# Main.net
KiCad netlist of a schematic drawn in Altium Designer
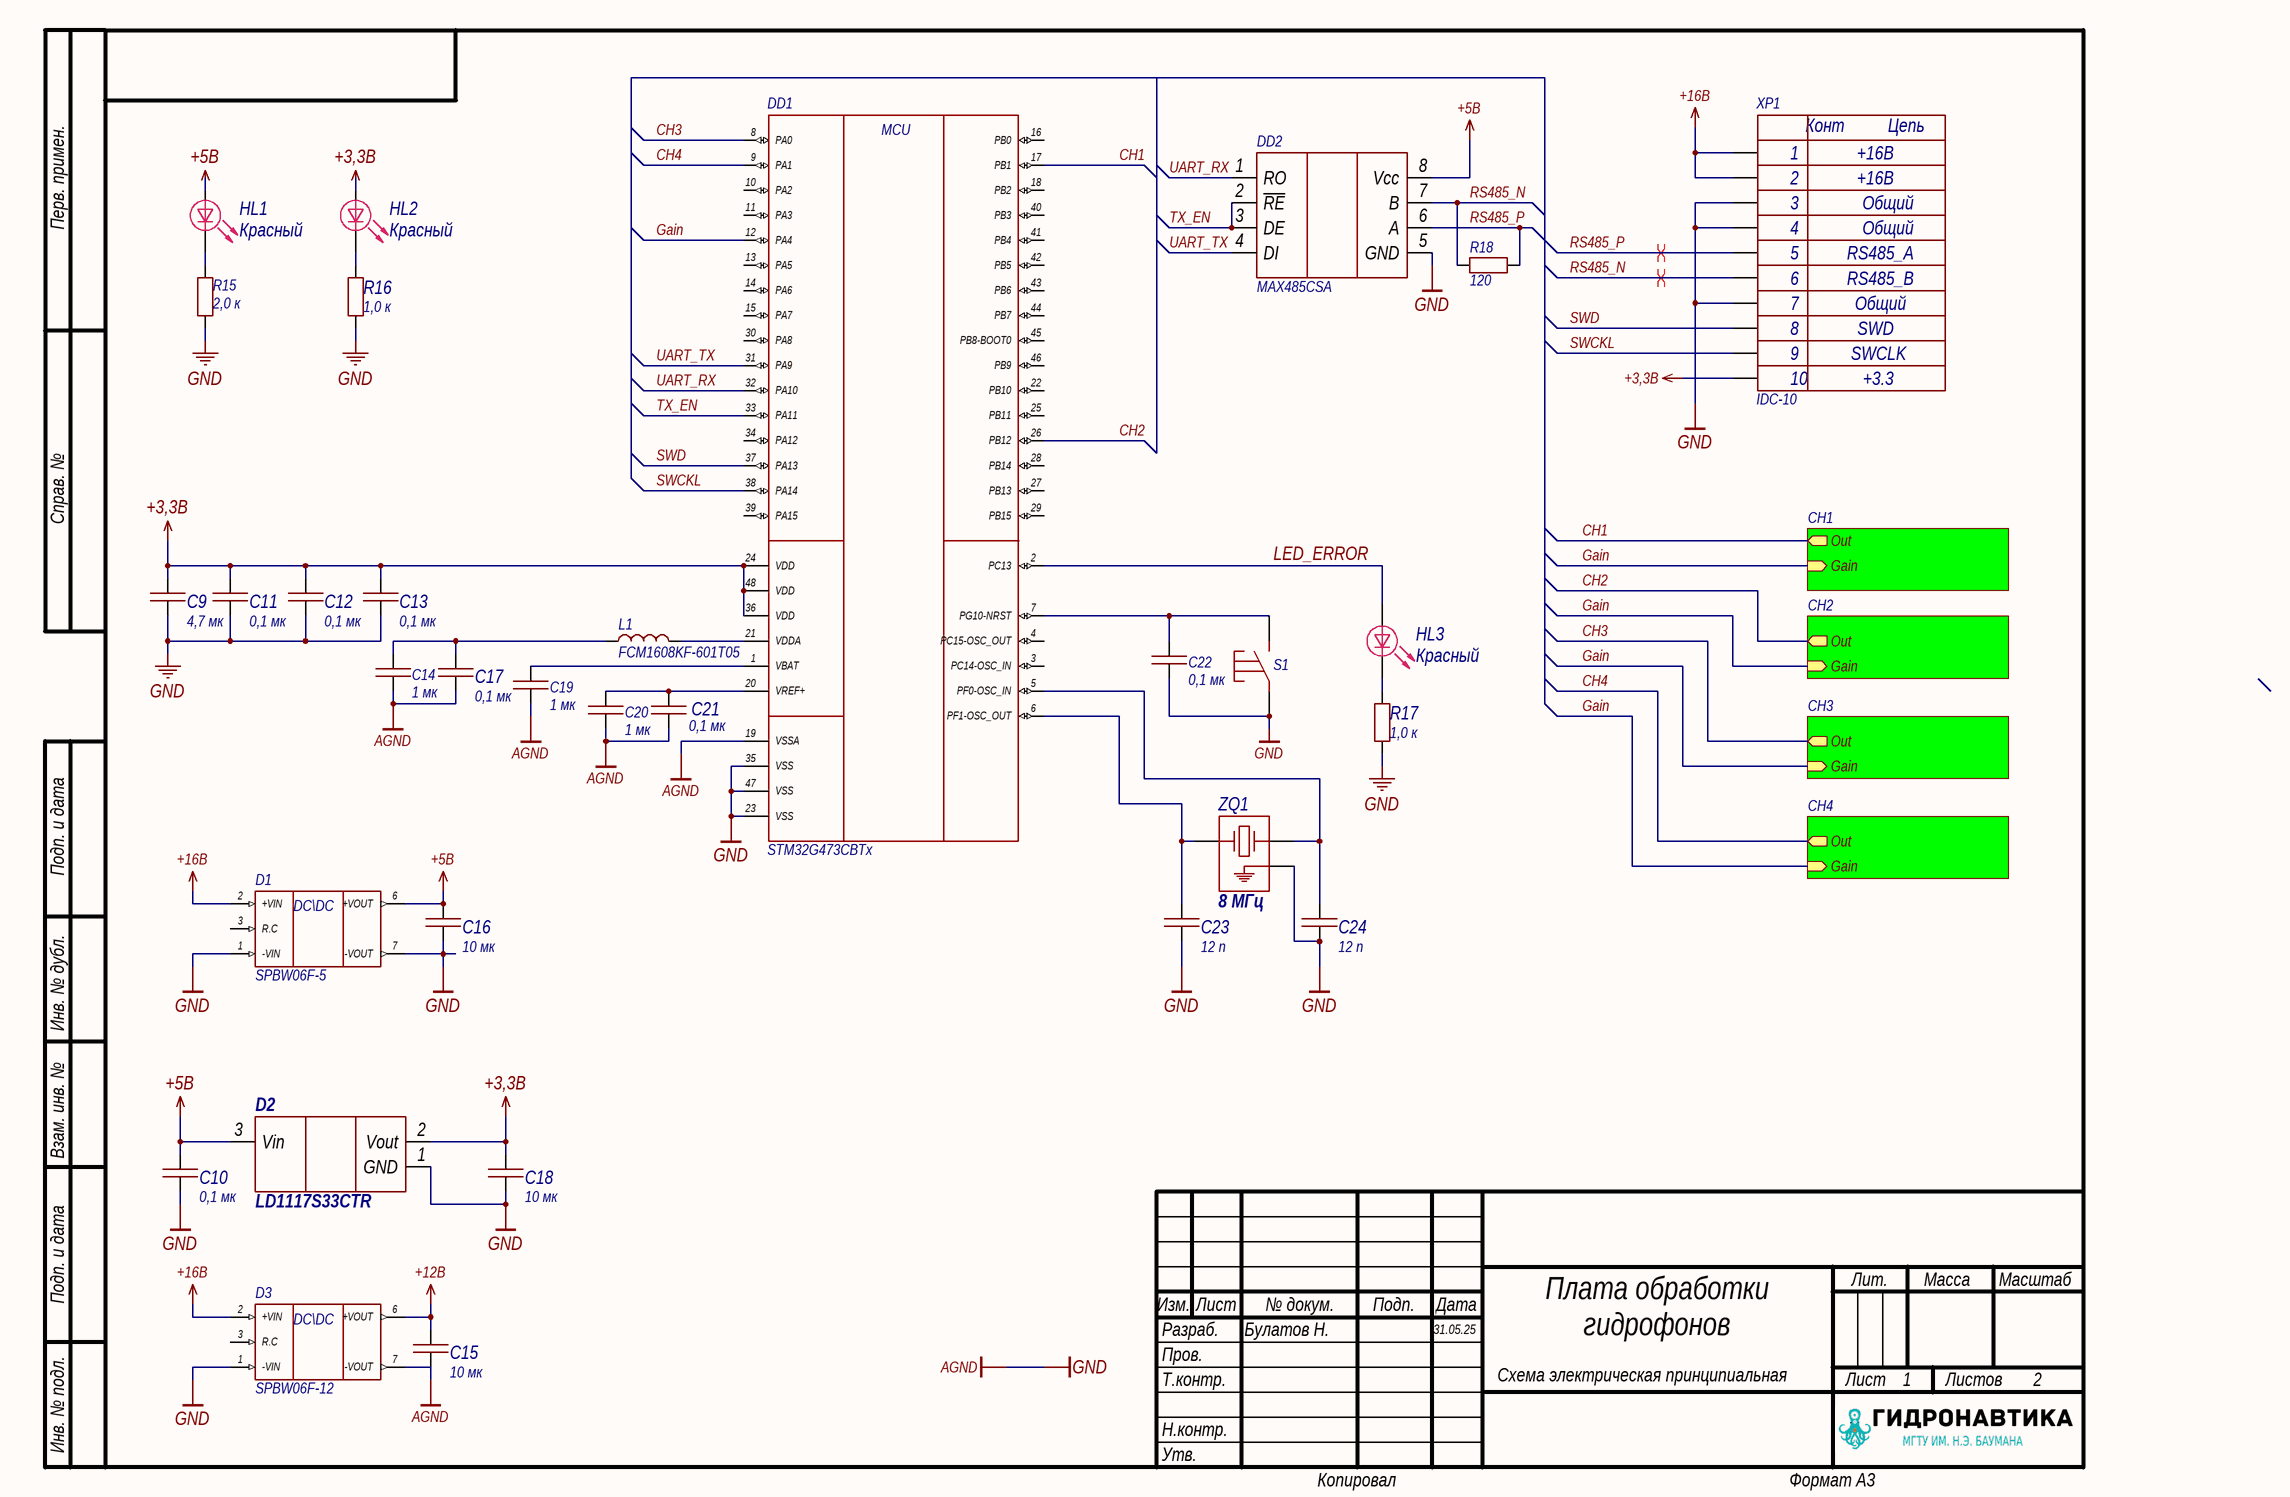
[diagram p0: Main.SchDoc]

(export (version "E")
  (design (tool "Eeschema 10.0.6"))
  (components
    (comp (ref "C9")
      (value "4,7 мк")
      (footprint "1206C")
      (description "Конденсатор")
      (fields (field (name "PART NUMBER") "Capacitor_4,7u_10_50V_X7R_1206C") (field (name "TOLERANCE") "0,1"))
      (libsource (lib "Hydrolib") (part "Capacitor"))
    )
    (comp (ref "C10")
      (value "0,1 мк")
      (footprint "0603C")
      (description "Конденсатор")
      (fields (field (name "PART NUMBER") "Capacitor_0,1u_10_50V_X7R_0603C") (field (name "TOLERANCE") "0,1"))
      (libsource (lib "Hydrolib") (part "Capacitor"))
    )
    (comp (ref "C11")
      (value "0,1 мк")
      (footprint "0603C")
      (description "Конденсатор")
      (fields (field (name "PART NUMBER") "Capacitor_0,1u_10_50V_X7R_0603C") (field (name "TOLERANCE") "0,1"))
      (libsource (lib "Hydrolib") (part "Capacitor"))
    )
    (comp (ref "C12")
      (value "0,1 мк")
      (footprint "0603C")
      (description "Конденсатор")
      (fields (field (name "PART NUMBER") "Capacitor_0,1u_10_50V_X7R_0603C") (field (name "TOLERANCE") "0,1"))
      (libsource (lib "Hydrolib") (part "Capacitor"))
    )
    (comp (ref "C13")
      (value "0,1 мк")
      (footprint "0603C")
      (description "Конденсатор")
      (fields (field (name "PART NUMBER") "Capacitor_0,1u_10_50V_X7R_0603C") (field (name "TOLERANCE") "0,1"))
      (libsource (lib "Hydrolib") (part "Capacitor"))
    )
    (comp (ref "C14")
      (value "1 мк")
      (footprint "0603C")
      (description "Конденсатор 0603C ёмкостью 1 мк 10%, 50 В, X7R")
      (fields (field (name "PART NUMBER") "Capacitor_1u_10_50V_X7R_0603C") (field (name "TOLERANCE") "10%"))
      (libsource (lib "Hydrolib") (part "Capacitor"))
    )
    (comp (ref "C15")
      (value "10 мк")
      (footprint "1210C")
      (description "Конденсатор")
      (fields (field (name "PART NUMBER") "Capacitor_10u_10_35V_X7R_1210C") (field (name "TOLERANCE") "0,1"))
      (libsource (lib "Hydrolib") (part "Capacitor"))
    )
    (comp (ref "C16")
      (value "10 мк")
      (footprint "1210C")
      (description "Конденсатор")
      (fields (field (name "PART NUMBER") "Capacitor_10u_10_35V_X7R_1210C") (field (name "TOLERANCE") "0,1"))
      (libsource (lib "Hydrolib") (part "Capacitor"))
    )
    (comp (ref "C17")
      (value "0,1 мк")
      (footprint "0603C")
      (description "Конденсатор")
      (fields (field (name "PART NUMBER") "Capacitor_0,1u_10_50V_X7R_0603C") (field (name "TOLERANCE") "0,1"))
      (libsource (lib "Hydrolib") (part "Capacitor"))
    )
    (comp (ref "C18")
      (value "10 мк")
      (footprint "1210C")
      (description "Конденсатор")
      (fields (field (name "PART NUMBER") "Capacitor_10u_10_35V_X7R_1210C") (field (name "TOLERANCE") "0,1"))
      (libsource (lib "Hydrolib") (part "Capacitor"))
    )
    (comp (ref "C19")
      (value "1 мк")
      (footprint "0603C")
      (description "Конденсатор 0603C ёмкостью 1 мк 10%, 50 В, X7R")
      (fields (field (name "PART NUMBER") "Capacitor_1u_10_50V_X7R_0603C") (field (name "TOLERANCE") "10%"))
      (libsource (lib "Hydrolib") (part "Capacitor"))
    )
    (comp (ref "C20")
      (value "1 мк")
      (footprint "0603C")
      (description "Конденсатор 0603C ёмкостью 1 мк 10%, 50 В, X7R")
      (fields (field (name "PART NUMBER") "Capacitor_1u_10_50V_X7R_0603C") (field (name "TOLERANCE") "10%"))
      (libsource (lib "Hydrolib") (part "Capacitor"))
    )
    (comp (ref "C21")
      (value "0,1 мк")
      (footprint "0603C")
      (description "Конденсатор")
      (fields (field (name "PART NUMBER") "Capacitor_0,1u_10_50V_X7R_0603C") (field (name "TOLERANCE") "0,1"))
      (libsource (lib "Hydrolib") (part "Capacitor"))
    )
    (comp (ref "C22")
      (value "0,1 мк")
      (footprint "0603C")
      (description "Конденсатор 0603C ёмкостью 0,1 мк 10%, 50 В, X7R")
      (fields (field (name "PART NUMBER") "Capacitor_0,1u_10_50V_X7R_0603C") (field (name "TOLERANCE") "10%"))
      (libsource (lib "Hydrolib") (part "Capacitor"))
    )
    (comp (ref "C23")
      (value "12 п")
      (footprint "0603C")
      (description "Конденсатор 12п")
      (fields (field (name "PART NUMBER") "Capacitor"))
      (libsource (lib "Hydrolib") (part "Capacitor"))
    )
    (comp (ref "C24")
      (value "12 п")
      (footprint "0603C")
      (description "Конденсатор 12п")
      (fields (field (name "PART NUMBER") "Capacitor"))
      (libsource (lib "Hydrolib") (part "Capacitor"))
    )
    (comp (ref "D1")
      (value "SPBW06F-5")
      (footprint "CONV_SPBW06F-12")
      (description "Isolated Module DC DC Converter 1 Output 12V - - - 500mA 9V - 36V Input")
      (fields (field (name "MF") "MEAN WELL") (field (name "MP") "SPBW06F-12"))
      (libsource (lib "SPBW06F-12") (part "SPBW06F-12"))
    )
    (comp (ref "D2")
      (value "LD1117S33CTR")
      (footprint "SOT223")
      (description "Линейный стабилизатор напряжения")
      (libsource (lib "Hydrolib") (part "LD1117S33CTR"))
    )
    (comp (ref "D3")
      (value "SPBW06F-12")
      (footprint "CONV_SPBW06F-12")
      (description "Isolated Module DC DC Converter 1 Output 12V - - - 500mA 9V - 36V Input")
      (fields (field (name "MF") "MEAN WELL"))
      (libsource (lib "SPBW06F-12") (part "SPBW06F-12"))
    )
    (comp (ref "DD1")
      (value "STM32G473CBTx")
      (footprint "LQFP48-7x7mm")
      (fields
        (field (name "MANUFACTURER_PART_NUMBER") "stm32g4_lqfp48_t1")
        (field (name "COPYRIGHT") "Copyright (C) 2016 Accelerated Designs. All rights reserved")
      )
      (libsource (lib "ST Microelectronics STM32 G4") (part "STM32G473CBTx"))
    )
    (comp (ref "DD2")
      (value "MAX485CSA")
      (footprint "SOIC-8")
      (description "RS-485 приёмопередатчик")
      (libsource (lib "Hydrolib") (part "MAX485CSA"))
    )
    (comp (ref "HL1")
      (value "LED")
      (footprint "0805D")
      (description "Светодиод")
      (fields (field (name "COLOR") "Красный"))
      (libsource (lib "Hydrolib") (part "LED"))
    )
    (comp (ref "HL2")
      (value "LED")
      (footprint "0805D")
      (description "Светодиод")
      (fields (field (name "COLOR") "Красный"))
      (libsource (lib "Hydrolib") (part "LED"))
    )
    (comp (ref "HL3")
      (value "LED")
      (footprint "0805D")
      (description "Светодиод")
      (fields (field (name "COLOR") "Красный"))
      (libsource (lib "Hydrolib") (part "LED"))
    )
    (comp (ref "L1")
      (value "FCM1608KF-601T05")
      (footprint "0603L")
      (description "Катушка индуктивности")
      (fields (field (name "PART NUMBER") "Inductance"))
      (libsource (lib "Hydrolib") (part "Inductance"))
    )
    (comp (ref "R15")
      (value "2,0 к")
      (footprint "0603R")
      (description "Резистор номиналом 2,0 кОм 1%")
      (fields (field (name "PART NUMBER") "Resistor_2.0k_1_0603") (field (name "TOLERANCE") "1%"))
      (libsource (lib "") (part "Resistor_1"))
    )
    (comp (ref "R16")
      (value "1,0 к")
      (footprint "0603R")
      (description "Резистор номиналом 1,0 кОм и точностью 1%")
      (fields (field (name "PART NUMBER") "Resistor_1.0k_1_0603") (field (name "TOLERANCE") "1%"))
      (libsource (lib "") (part "Resistor_1"))
    )
    (comp (ref "R17")
      (value "1,0 к")
      (footprint "0603R")
      (description "Резистор номиналом 1,0 кОм и точностью 1%")
      (fields (field (name "PART NUMBER") "Resistor_1.0k_1_0603") (field (name "TOLERANCE") "1%"))
      (libsource (lib "") (part "Resistor_1"))
    )
    (comp (ref "R18")
      (value "120")
      (footprint "0603R")
      (description "Резистор номиналом 120 Ом 1%")
      (fields (field (name "PART NUMBER") "Resistor_120_1_0603") (field (name "TOLERANCE") "1%"))
      (libsource (lib "Hydrolib") (part "Resistor"))
    )
    (comp (ref "S1")
      (value "TSS-TD-19XA-XTR")
      (footprint "TSS-TD-19XA-XTR")
      (description "Тактовая кнопка")
      (fields (field (name "АВТОР") "glebmih"))
      (libsource (lib "Hydrolib") (part "Tact_button"))
    )
    (comp (ref "XP1")
      (value "IDC-10")
      (footprint "IDC-10")
      (description "10-пиновый разъём с ключём")
      (fields
        (field (name "VALUE1") "+16В")
        (field (name "VALUE2") "+16В")
        (field (name "VALUE3") "Общий")
        (field (name "VALUE4") "Общий")
        (field (name "VALUE5") "RS485_A")
        (field (name "VALUE6") "RS485_B")
        (field (name "VALUE7") "Общий")
        (field (name "VALUE8") "SWD")
        (field (name "VALUE9") "SWCLK")
        (field (name "VALUE10") "+3.3")
      )
      (libsource (lib "Hydrolib") (part "Conn_10pin"))
    )
    (comp (ref "ZQ1")
      (value "8 МГц")
      (footprint "QSMD3.2x2.5")
      (description "Кварцевый резонатор с входом земли")
      (fields (field (name "PART NUMBER") "XTAL_GND"))
      (libsource (lib "Hydrolib") (part "XTAL_GND"))
    )
  )
  (nets
    (net (code "1") (name "+3,3В") (class "Default")
      (node (ref "C11") (pin "2") (pinfunction "2_2") (pintype "passive"))
      (node (ref "C12") (pin "2") (pinfunction "2_2") (pintype "passive"))
      (node (ref "C13") (pin "2") (pinfunction "2_2") (pintype "passive"))
      (node (ref "C18") (pin "2") (pinfunction "2_2") (pintype "passive"))
      (node (ref "C9") (pin "2") (pinfunction "2_2") (pintype "passive"))
      (node (ref "D2") (pin "2") (pinfunction "Vout_2") (pintype "passive"))
      (node (ref "DD1") (pin "24") (pinfunction "VDD_24") (pintype "power_in"))
      (node (ref "DD1") (pin "36") (pinfunction "VDD_36") (pintype "power_in"))
      (node (ref "DD1") (pin "48") (pinfunction "VDD_48") (pintype "power_in"))
      (node (ref "HL2") (pin "1") (pinfunction "1_1") (pintype "passive"))
      (node (ref "XP1") (pin "10") (pinfunction "10_10") (pintype "passive"))
    )
    (net (code "2") (name "+5В") (class "Default")
      (node (ref "C10") (pin "2") (pinfunction "2_2") (pintype "passive"))
      (node (ref "C16") (pin "2") (pinfunction "2_2") (pintype "passive"))
      (node (ref "D1") (pin "6") (pinfunction "+VOUT_6") (pintype "output"))
      (node (ref "D2") (pin "3") (pinfunction "Vin_3") (pintype "passive"))
      (node (ref "DD2") (pin "8") (pinfunction "Vcc_8") (pintype "passive"))
      (node (ref "HL1") (pin "1") (pinfunction "1_1") (pintype "passive"))
    )
    (net (code "3") (name "+12В") (class "Default")
      (node (ref "C15") (pin "2") (pinfunction "2_2") (pintype "passive"))
      (node (ref "D3") (pin "6") (pinfunction "+VOUT_6") (pintype "output"))
    )
    (net (code "4") (name "+16В") (class "Default")
      (node (ref "D1") (pin "2") (pinfunction "+VIN_2") (pintype "input"))
      (node (ref "D3") (pin "2") (pinfunction "+VIN_2") (pintype "input"))
      (node (ref "XP1") (pin "1") (pinfunction "1_1") (pintype "passive"))
      (node (ref "XP1") (pin "2") (pinfunction "2_2") (pintype "passive"))
    )
    (net (code "5") (name "/CH1") (class "Default")
      (node (ref "DD1") (pin "17") (pinfunction "PB1_17") (pintype "bidirectional"))
    )
    (net (code "6") (name "/CH2") (class "Default")
      (node (ref "DD1") (pin "26") (pinfunction "PB12_26") (pintype "bidirectional"))
    )
    (net (code "7") (name "/CH3") (class "Default")
      (node (ref "DD1") (pin "8") (pinfunction "PA0_8") (pintype "bidirectional"))
    )
    (net (code "8") (name "/CH4") (class "Default")
      (node (ref "DD1") (pin "9") (pinfunction "PA1_9") (pintype "bidirectional"))
    )
    (net (code "9") (name "/Gain") (class "Default")
      (node (ref "DD1") (pin "12") (pinfunction "PA4_12") (pintype "bidirectional"))
    )
    (net (code "10") (name "/LED_ERROR") (class "Default")
      (node (ref "DD1") (pin "2") (pinfunction "PC13_2") (pintype "bidirectional"))
      (node (ref "HL3") (pin "1") (pinfunction "1_1") (pintype "passive"))
    )
    (net (code "11") (name "/RS485_N") (class "Default")
      (node (ref "DD2") (pin "7") (pinfunction "B_7") (pintype "passive"))
      (node (ref "R18") (pin "2") (pinfunction "2_2") (pintype "passive"))
      (node (ref "XP1") (pin "6") (pinfunction "6_6") (pintype "passive"))
    )
    (net (code "12") (name "/RS485_P") (class "Default")
      (node (ref "DD2") (pin "6") (pinfunction "A_6") (pintype "passive"))
      (node (ref "R18") (pin "1") (pinfunction "1_1") (pintype "passive"))
      (node (ref "XP1") (pin "5") (pinfunction "5_5") (pintype "passive"))
    )
    (net (code "13") (name "/SWCKL") (class "Default")
      (node (ref "DD1") (pin "38") (pinfunction "PA14_38") (pintype "bidirectional"))
      (node (ref "XP1") (pin "9") (pinfunction "9_9") (pintype "passive"))
    )
    (net (code "14") (name "/SWD") (class "Default")
      (node (ref "DD1") (pin "37") (pinfunction "PA13_37") (pintype "bidirectional"))
      (node (ref "XP1") (pin "8") (pinfunction "8_8") (pintype "passive"))
    )
    (net (code "15") (name "/TX_EN") (class "Default")
      (node (ref "DD1") (pin "33") (pinfunction "PA11_33") (pintype "bidirectional"))
      (node (ref "DD2") (pin "2") (pinfunction "RE_2") (pintype "passive"))
      (node (ref "DD2") (pin "3") (pinfunction "DE_3") (pintype "passive"))
    )
    (net (code "16") (name "/UART_RX") (class "Default")
      (node (ref "DD1") (pin "32") (pinfunction "PA10_32") (pintype "bidirectional"))
      (node (ref "DD2") (pin "1") (pinfunction "RO_1") (pintype "passive"))
    )
    (net (code "17") (name "/UART_TX") (class "Default")
      (node (ref "DD1") (pin "31") (pinfunction "PA9_31") (pintype "bidirectional"))
      (node (ref "DD2") (pin "4") (pinfunction "DI_4") (pintype "passive"))
    )
    (net (code "18") (name "AGND") (class "Default")
      (node (ref "C10") (pin "1") (pinfunction "1_1") (pintype "passive"))
      (node (ref "C11") (pin "1") (pinfunction "1_1") (pintype "passive"))
      (node (ref "C12") (pin "1") (pinfunction "1_1") (pintype "passive"))
      (node (ref "C13") (pin "1") (pinfunction "1_1") (pintype "passive"))
      (node (ref "C14") (pin "1") (pinfunction "1_1") (pintype "passive"))
      (node (ref "C15") (pin "1") (pinfunction "1_1") (pintype "passive"))
      (node (ref "C16") (pin "1") (pinfunction "1_1") (pintype "passive"))
      (node (ref "C17") (pin "1") (pinfunction "1_1") (pintype "passive"))
      (node (ref "C18") (pin "1") (pinfunction "1_1") (pintype "passive"))
      (node (ref "C19") (pin "1") (pinfunction "1_1") (pintype "passive"))
      (node (ref "C20") (pin "1") (pinfunction "1_1") (pintype "passive"))
      (node (ref "C21") (pin "1") (pinfunction "1_1") (pintype "passive"))
      (node (ref "C22") (pin "1") (pinfunction "1_1") (pintype "passive"))
      (node (ref "C23") (pin "1") (pinfunction "1_1") (pintype "passive"))
      (node (ref "C24") (pin "1") (pinfunction "1_1") (pintype "passive"))
      (node (ref "C9") (pin "1") (pinfunction "1_1") (pintype "passive"))
      (node (ref "D1") (pin "1") (pinfunction "-VIN_1") (pintype "input"))
      (node (ref "D1") (pin "7") (pinfunction "-VOUT_7") (pintype "output"))
      (node (ref "D2") (pin "1") (pinfunction "GND_1") (pintype "passive"))
      (node (ref "D3") (pin "1") (pinfunction "-VIN_1") (pintype "input"))
      (node (ref "D3") (pin "7") (pinfunction "-VOUT_7") (pintype "output"))
      (node (ref "DD1") (pin "19") (pinfunction "VSSA_19") (pintype "power_in"))
      (node (ref "DD1") (pin "23") (pinfunction "VSS_23") (pintype "power_in"))
      (node (ref "DD1") (pin "35") (pinfunction "VSS_35") (pintype "power_in"))
      (node (ref "DD1") (pin "47") (pinfunction "VSS_47") (pintype "power_in"))
      (node (ref "DD2") (pin "5") (pinfunction "GND_5") (pintype "passive"))
      (node (ref "R15") (pin "1") (pinfunction "1_1") (pintype "passive"))
      (node (ref "R16") (pin "1") (pinfunction "1_1") (pintype "passive"))
      (node (ref "R17") (pin "1") (pinfunction "1_1") (pintype "passive"))
      (node (ref "S1") (pin "1") (pinfunction "1_1") (pintype "passive"))
      (node (ref "XP1") (pin "3") (pinfunction "3_3") (pintype "passive"))
      (node (ref "XP1") (pin "4") (pinfunction "4_4") (pintype "passive"))
      (node (ref "XP1") (pin "7") (pinfunction "7_7") (pintype "passive"))
      (node (ref "ZQ1") (pin "3") (pinfunction "3_3") (pintype "passive"))
    )
    (net (code "19") (name "Net-(C14-Pad2)") (class "Default")
      (node (ref "C14") (pin "2") (pinfunction "2_2") (pintype "passive"))
      (node (ref "C17") (pin "2") (pinfunction "2_2") (pintype "passive"))
      (node (ref "L1") (pin "1") (pinfunction "1_1") (pintype "passive"))
    )
    (net (code "20") (name "Net-(DD1-PF0-OSC_IN)") (class "Default")
      (node (ref "C24") (pin "2") (pinfunction "2_2") (pintype "passive"))
      (node (ref "DD1") (pin "5") (pinfunction "PF0-OSC_IN_5") (pintype "bidirectional"))
      (node (ref "ZQ1") (pin "2") (pinfunction "2_2") (pintype "passive"))
    )
    (net (code "21") (name "Net-(DD1-PF1-OSC_OUT)") (class "Default")
      (node (ref "C23") (pin "2") (pinfunction "2_2") (pintype "passive"))
      (node (ref "DD1") (pin "6") (pinfunction "PF1-OSC_OUT_6") (pintype "bidirectional"))
      (node (ref "ZQ1") (pin "1") (pinfunction "1_1") (pintype "passive"))
    )
    (net (code "22") (name "Net-(DD1-PG10-NRST)") (class "Default")
      (node (ref "C22") (pin "2") (pinfunction "2_2") (pintype "passive"))
      (node (ref "DD1") (pin "7") (pinfunction "PG10-NRST_7") (pintype "bidirectional"))
      (node (ref "S1") (pin "2") (pinfunction "2_2") (pintype "passive"))
    )
    (net (code "23") (name "Net-(DD1-VBAT)") (class "Default")
      (node (ref "C19") (pin "2") (pinfunction "2_2") (pintype "passive"))
      (node (ref "DD1") (pin "1") (pinfunction "VBAT_1") (pintype "power_in"))
    )
    (net (code "24") (name "Net-(DD1-VDDA)") (class "Default")
      (node (ref "DD1") (pin "21") (pinfunction "VDDA_21") (pintype "power_in"))
      (node (ref "L1") (pin "2") (pinfunction "2_2") (pintype "passive"))
    )
    (net (code "25") (name "Net-(DD1-VREF+)") (class "Default")
      (node (ref "C20") (pin "2") (pinfunction "2_2") (pintype "passive"))
      (node (ref "C21") (pin "2") (pinfunction "2_2") (pintype "passive"))
      (node (ref "DD1") (pin "20") (pinfunction "VREF+_20") (pintype "power_in"))
    )
    (net (code "26") (name "Net-(HL1-Pad2)") (class "Default")
      (node (ref "HL1") (pin "2") (pinfunction "2_2") (pintype "passive"))
      (node (ref "R15") (pin "2") (pinfunction "2_2") (pintype "passive"))
    )
    (net (code "27") (name "Net-(HL2-Pad2)") (class "Default")
      (node (ref "HL2") (pin "2") (pinfunction "2_2") (pintype "passive"))
      (node (ref "R16") (pin "2") (pinfunction "2_2") (pintype "passive"))
    )
    (net (code "28") (name "Net-(HL3-Pad2)") (class "Default")
      (node (ref "HL3") (pin "2") (pinfunction "2_2") (pintype "passive"))
      (node (ref "R17") (pin "2") (pinfunction "2_2") (pintype "passive"))
    )
    (net (code "29") (name "unconnected-(D1-R.C-Pad3)") (class "Default")
      (node (ref "D1") (pin "3") (pinfunction "R.C_3") (pintype "input"))
    )
    (net (code "30") (name "unconnected-(D3-R.C-Pad3)") (class "Default")
      (node (ref "D3") (pin "3") (pinfunction "R.C_3") (pintype "input"))
    )
    (net (code "31") (name "unconnected-(DD1-PA2-Pad10)") (class "Default")
      (node (ref "DD1") (pin "10") (pinfunction "PA2_10") (pintype "bidirectional"))
    )
    (net (code "32") (name "unconnected-(DD1-PA3-Pad11)") (class "Default")
      (node (ref "DD1") (pin "11") (pinfunction "PA3_11") (pintype "bidirectional"))
    )
    (net (code "33") (name "unconnected-(DD1-PA5-Pad13)") (class "Default")
      (node (ref "DD1") (pin "13") (pinfunction "PA5_13") (pintype "bidirectional"))
    )
    (net (code "34") (name "unconnected-(DD1-PA6-Pad14)") (class "Default")
      (node (ref "DD1") (pin "14") (pinfunction "PA6_14") (pintype "bidirectional"))
    )
    (net (code "35") (name "unconnected-(DD1-PA7-Pad15)") (class "Default")
      (node (ref "DD1") (pin "15") (pinfunction "PA7_15") (pintype "bidirectional"))
    )
    (net (code "36") (name "unconnected-(DD1-PA8-Pad30)") (class "Default")
      (node (ref "DD1") (pin "30") (pinfunction "PA8_30") (pintype "bidirectional"))
    )
    (net (code "37") (name "unconnected-(DD1-PA12-Pad34)") (class "Default")
      (node (ref "DD1") (pin "34") (pinfunction "PA12_34") (pintype "bidirectional"))
    )
    (net (code "38") (name "unconnected-(DD1-PA15-Pad39)") (class "Default")
      (node (ref "DD1") (pin "39") (pinfunction "PA15_39") (pintype "bidirectional"))
    )
    (net (code "39") (name "unconnected-(DD1-PB0-Pad16)") (class "Default")
      (node (ref "DD1") (pin "16") (pinfunction "PB0_16") (pintype "bidirectional"))
    )
    (net (code "40") (name "unconnected-(DD1-PB2-Pad18)") (class "Default")
      (node (ref "DD1") (pin "18") (pinfunction "PB2_18") (pintype "bidirectional"))
    )
    (net (code "41") (name "unconnected-(DD1-PB3-Pad40)") (class "Default")
      (node (ref "DD1") (pin "40") (pinfunction "PB3_40") (pintype "bidirectional"))
    )
    (net (code "42") (name "unconnected-(DD1-PB4-Pad41)") (class "Default")
      (node (ref "DD1") (pin "41") (pinfunction "PB4_41") (pintype "bidirectional"))
    )
    (net (code "43") (name "unconnected-(DD1-PB5-Pad42)") (class "Default")
      (node (ref "DD1") (pin "42") (pinfunction "PB5_42") (pintype "bidirectional"))
    )
    (net (code "44") (name "unconnected-(DD1-PB6-Pad43)") (class "Default")
      (node (ref "DD1") (pin "43") (pinfunction "PB6_43") (pintype "bidirectional"))
    )
    (net (code "45") (name "unconnected-(DD1-PB7-Pad44)") (class "Default")
      (node (ref "DD1") (pin "44") (pinfunction "PB7_44") (pintype "bidirectional"))
    )
    (net (code "46") (name "unconnected-(DD1-PB8-BOOT0-Pad45)") (class "Default")
      (node (ref "DD1") (pin "45") (pinfunction "PB8-BOOT0_45") (pintype "bidirectional"))
    )
    (net (code "47") (name "unconnected-(DD1-PB9-Pad46)") (class "Default")
      (node (ref "DD1") (pin "46") (pinfunction "PB9_46") (pintype "bidirectional"))
    )
    (net (code "48") (name "unconnected-(DD1-PB10-Pad22)") (class "Default")
      (node (ref "DD1") (pin "22") (pinfunction "PB10_22") (pintype "bidirectional"))
    )
    (net (code "49") (name "unconnected-(DD1-PB11-Pad25)") (class "Default")
      (node (ref "DD1") (pin "25") (pinfunction "PB11_25") (pintype "bidirectional"))
    )
    (net (code "50") (name "unconnected-(DD1-PB13-Pad27)") (class "Default")
      (node (ref "DD1") (pin "27") (pinfunction "PB13_27") (pintype "bidirectional"))
    )
    (net (code "51") (name "unconnected-(DD1-PB14-Pad28)") (class "Default")
      (node (ref "DD1") (pin "28") (pinfunction "PB14_28") (pintype "bidirectional"))
    )
    (net (code "52") (name "unconnected-(DD1-PB15-Pad29)") (class "Default")
      (node (ref "DD1") (pin "29") (pinfunction "PB15_29") (pintype "bidirectional"))
    )
    (net (code "53") (name "unconnected-(DD1-PC14-OSC_IN-Pad3)") (class "Default")
      (node (ref "DD1") (pin "3") (pinfunction "PC14-OSC_IN_3") (pintype "bidirectional"))
    )
    (net (code "54") (name "unconnected-(DD1-PC15-OSC_OUT-Pad4)") (class "Default")
      (node (ref "DD1") (pin "4") (pinfunction "PC15-OSC_OUT_4") (pintype "bidirectional"))
    )
  )
)
